# Sheet1.net
KiCad netlist of a schematic drawn in Altium Designer
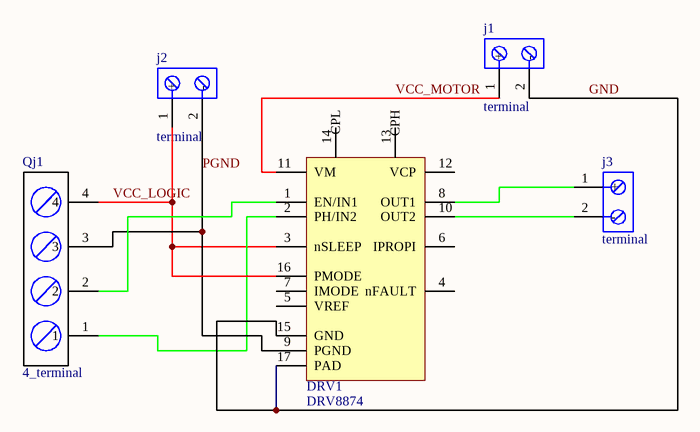
[diagram p0: Sheet1.SchDoc]

(export (version "E")
  (design (tool "Eeschema 10.0.6"))
  (components
    (comp (ref "DRV1")
      (value "DRV8874")
      (footprint "DRV8874")
      (description "Brush DC Motor Controller, 6A, PDSO16")
      (fields
        (field (name "MANUFACTURER") "Texas Instruments")
        (field (name "MANUFACTURER PART NUMBER") "DRV8874QPWPRQ1")
      )
      (libsource (lib "my_integrated_lib") (part "DRV8874QPWPRQ1"))
    )
    (comp (ref "j1")
      (value "terminal")
      (footprint "terminal")
      (description "Barrier Strip Terminal Block")
      (fields
        (field (name "MANUFACTURER") "Wurth Electronics")
        (field (name "MANUFACTURER PART NUMBER") "691137710002")
      )
      (libsource (lib "my_integrated_lib") (part "691137710002"))
    )
    (comp (ref "j2")
      (value "terminal")
      (footprint "terminal")
      (description "Barrier Strip Terminal Block")
      (fields
        (field (name "MANUFACTURER") "Wurth Electronics")
        (field (name "MANUFACTURER PART NUMBER") "691137710002")
      )
      (libsource (lib "my_integrated_lib") (part "691137710002"))
    )
    (comp (ref "j3")
      (value "terminal")
      (footprint "terminal")
      (description "Barrier Strip Terminal Block")
      (fields
        (field (name "MANUFACTURER") "Wurth Electronics")
        (field (name "MANUFACTURER PART NUMBER") "691137710002")
      )
      (libsource (lib "my_integrated_lib") (part "691137710002"))
    )
    (comp (ref "Qj1")
      (value "4_terminal")
      (footprint "4 position terminal block")
      (description "Barrier Strip Terminal Block, 12A, 1.5mm2, 1 Row(s), 1 Deck(s)")
      (fields
        (field (name "MANUFACTURER") "Phoenix Contact")
        (field (name "MANUFACTURER PART NUMBER") "1934887")
        (field (name "SAFETY APPROVAL") "UL")
      )
      (libsource (lib "my_integrated_lib") (part "1934887"))
    )
  )
  (nets
    (net (code "1") (name "/GND") (class "Default")
      (node (ref "DRV1") (pin "15") (pinfunction "GND_15") (pintype "passive"))
      (node (ref "DRV1") (pin "17") (pinfunction "PAD_17") (pintype "passive"))
      (node (ref "j1") (pin "2") (pinfunction "-_2") (pintype "passive"))
    )
    (net (code "2") (name "/PGND") (class "Default")
      (node (ref "DRV1") (pin "9") (pinfunction "PGND_9") (pintype "passive"))
      (node (ref "Qj1") (pin "3") (pinfunction "3_3") (pintype "passive"))
      (node (ref "j2") (pin "2") (pinfunction "-_2") (pintype "passive"))
    )
    (net (code "3") (name "/VCC_LOGIC") (class "Default")
      (node (ref "DRV1") (pin "16") (pinfunction "PMODE_16") (pintype "passive"))
      (node (ref "DRV1") (pin "3") (pinfunction "nSLEEP_3") (pintype "passive"))
      (node (ref "Qj1") (pin "4") (pinfunction "4_4") (pintype "passive"))
      (node (ref "j2") (pin "1") (pinfunction "+_1") (pintype "passive"))
    )
    (net (code "4") (name "/VCC_MOTOR") (class "Default")
      (node (ref "DRV1") (pin "11") (pinfunction "VM_11") (pintype "passive"))
      (node (ref "j1") (pin "1") (pinfunction "+_1") (pintype "passive"))
    )
    (net (code "5") (name "Net-(DRV1-EN{slash}IN1)") (class "Default")
      (node (ref "DRV1") (pin "1") (pinfunction "EN/IN1_1") (pintype "passive"))
      (node (ref "Qj1") (pin "2") (pinfunction "2_2") (pintype "passive"))
    )
    (net (code "6") (name "Net-(DRV1-OUT1)") (class "Default")
      (node (ref "DRV1") (pin "8") (pinfunction "OUT1_8") (pintype "passive"))
      (node (ref "j3") (pin "1") (pinfunction "+_1") (pintype "passive"))
    )
    (net (code "7") (name "Net-(DRV1-OUT2)") (class "Default")
      (node (ref "DRV1") (pin "10") (pinfunction "OUT2_10") (pintype "passive"))
      (node (ref "j3") (pin "2") (pinfunction "-_2") (pintype "passive"))
    )
    (net (code "8") (name "Net-(DRV1-PH{slash}IN2)") (class "Default")
      (node (ref "DRV1") (pin "2") (pinfunction "PH/IN2_2") (pintype "passive"))
      (node (ref "Qj1") (pin "1") (pinfunction "1_1") (pintype "passive"))
    )
    (net (code "9") (name "unconnected-(DRV1-CPH-Pad13)") (class "Default")
      (node (ref "DRV1") (pin "13") (pinfunction "CPH_13") (pintype "passive"))
    )
    (net (code "10") (name "unconnected-(DRV1-CPL-Pad14)") (class "Default")
      (node (ref "DRV1") (pin "14") (pinfunction "CPL_14") (pintype "passive"))
    )
    (net (code "11") (name "unconnected-(DRV1-IMODE-Pad7)") (class "Default")
      (node (ref "DRV1") (pin "7") (pinfunction "IMODE_7") (pintype "passive"))
    )
    (net (code "12") (name "unconnected-(DRV1-IPROPI-Pad6)") (class "Default")
      (node (ref "DRV1") (pin "6") (pinfunction "IPROPI_6") (pintype "passive"))
    )
    (net (code "13") (name "unconnected-(DRV1-VCP-Pad12)") (class "Default")
      (node (ref "DRV1") (pin "12") (pinfunction "VCP_12") (pintype "passive"))
    )
    (net (code "14") (name "unconnected-(DRV1-VREF-Pad5)") (class "Default")
      (node (ref "DRV1") (pin "5") (pinfunction "VREF_5") (pintype "passive"))
    )
    (net (code "15") (name "unconnected-(DRV1-nFAULT-Pad4)") (class "Default")
      (node (ref "DRV1") (pin "4") (pinfunction "nFAULT_4") (pintype "passive"))
    )
  )
)
